# INA169_Breakout.net
KiCad netlist of a schematic drawn in EAGLE
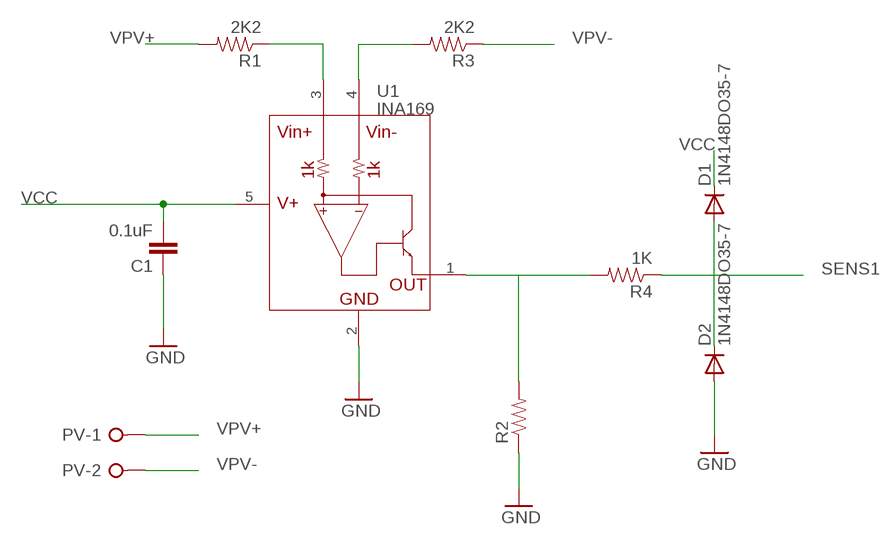
[diagram p0: schematic, sheet 1]
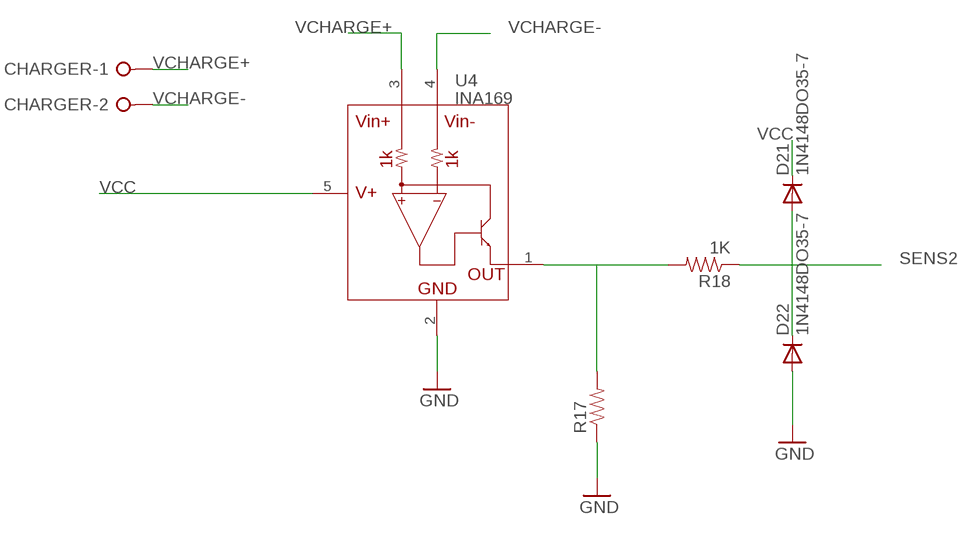
[diagram p1: schematic, sheet 2]
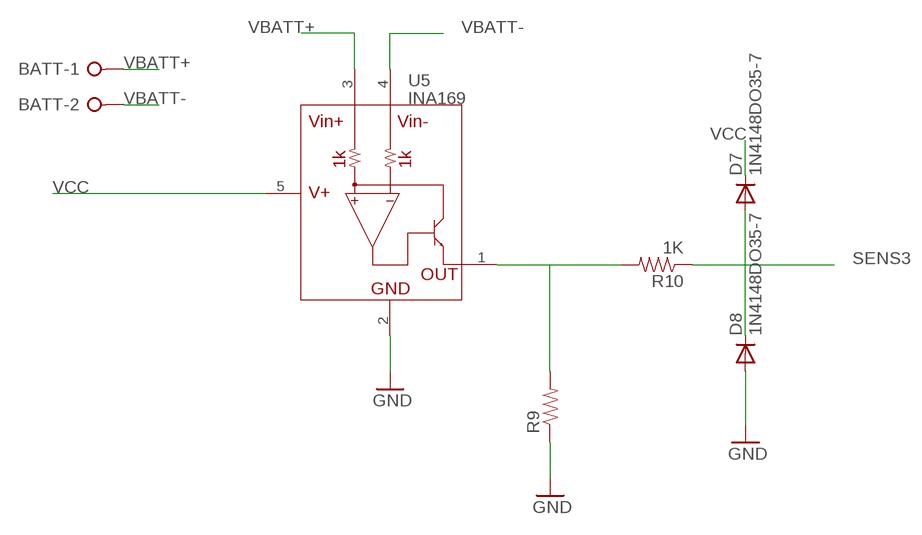
[diagram p2: schematic, sheet 3]
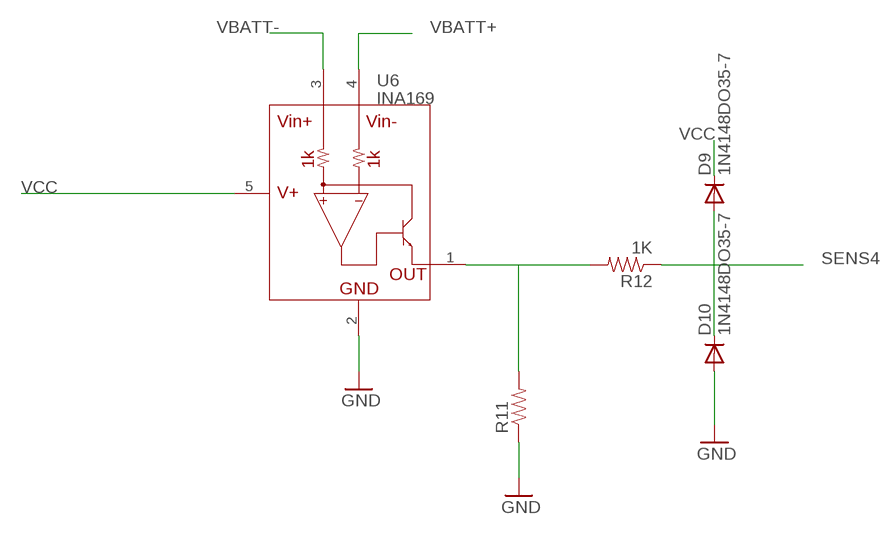
[diagram p3: schematic, sheet 4]
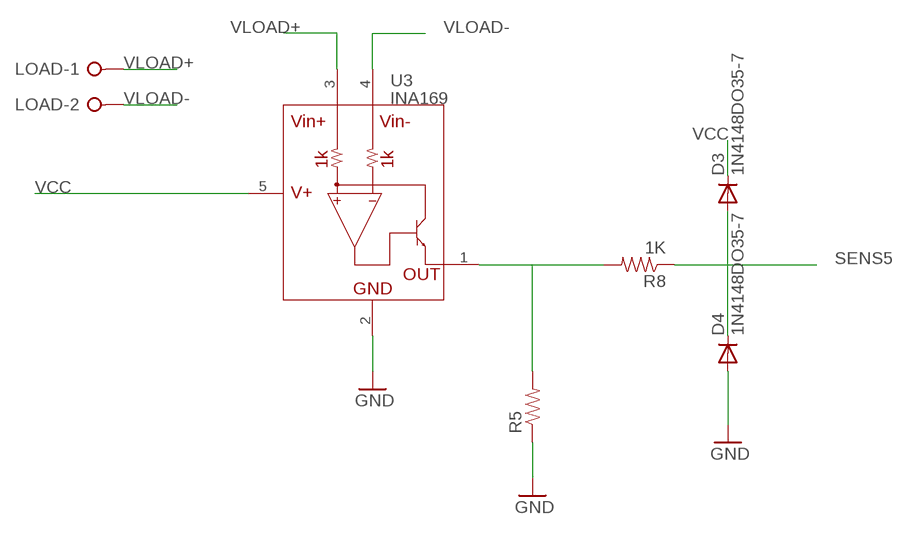
[diagram p4: schematic, sheet 5]
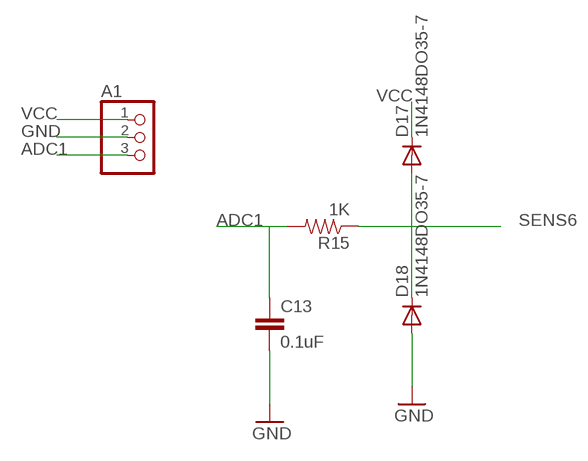
[diagram p5: schematic, sheet 6]
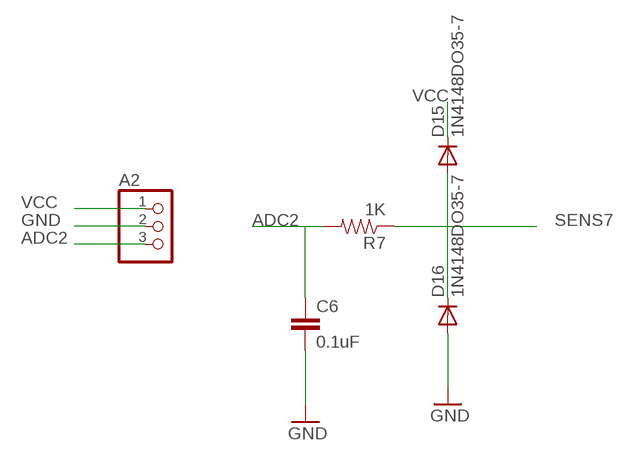
[diagram p6: schematic, sheet 7]
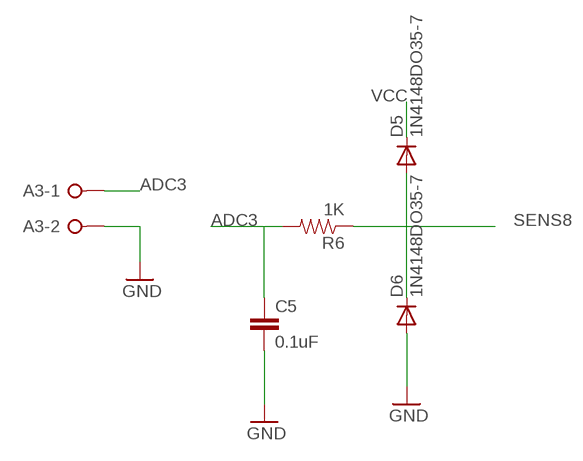
[diagram p7: schematic, sheet 8]
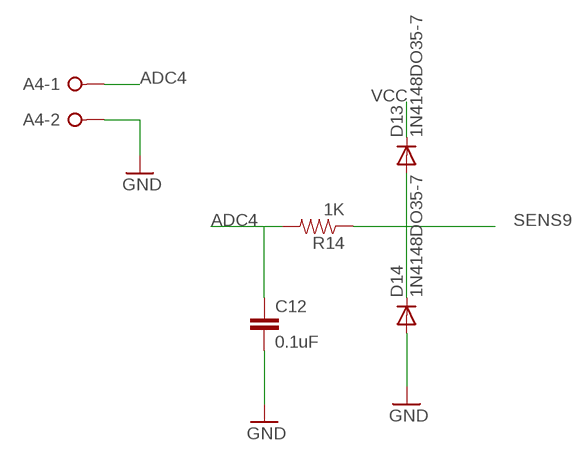
[diagram p8: schematic, sheet 9]
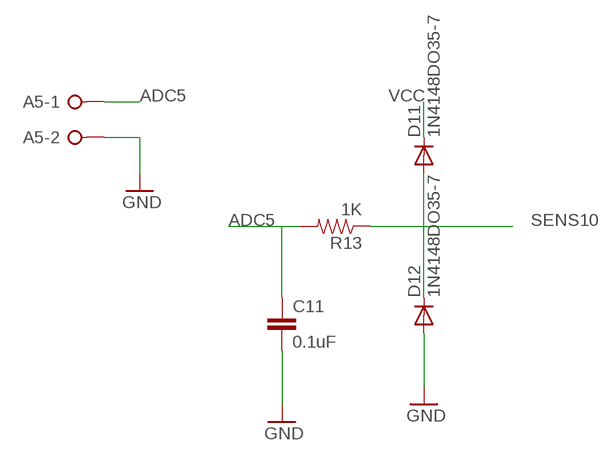
[diagram p9: schematic, sheet 10]
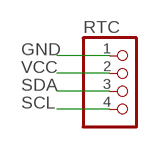
[diagram p10: schematic, sheet 11]
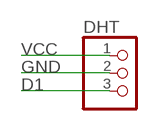
[diagram p11: schematic, sheet 12]
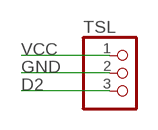
[diagram p12: schematic, sheet 13]
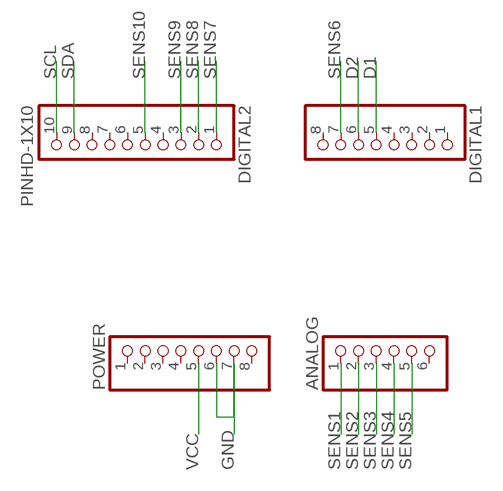
[diagram p13: schematic, sheet 14]

(export (version "E")
  (design (tool "Eeschema 10.0.6"))
  (components
    (comp (ref "CHARGER")
      (value "W237-02P")
      (footprint "eagle-import:W237-132")
      (libsource (lib "eagle-import") (part "W237-02P"))
    )
    (comp (ref "D21")
      (value "1N4148DO35-7")
      (footprint "eagle-import:DO35-7")
      (libsource (lib "eagle-import") (part "1N4148DO35-7"))
    )
    (comp (ref "D22")
      (value "1N4148DO35-7")
      (footprint "eagle-import:DO35-7")
      (libsource (lib "eagle-import") (part "1N4148DO35-7"))
    )
    (comp (ref "R17")
      (value "RESISTOR0603")
      (footprint "eagle-import:0603-RES")
      (fields (field (name "TOL") "1%"))
      (libsource (lib "eagle-import") (part "RESISTOR0603"))
    )
    (comp (ref "R18")
      (value "1K")
      (footprint "eagle-import:0603-RES")
      (fields (field (name "TOL") "1%"))
      (libsource (lib "eagle-import") (part "RESISTOR0603"))
    )
    (comp (ref "U4")
      (value "INA169")
      (footprint "eagle-import:SOT23-5")
      (libsource (lib "eagle-import") (part "INA169"))
    )
    (comp (ref "A2")
      (value "PINHD-1X3")
      (footprint "eagle-import:1X03")
      (libsource (lib "eagle-import") (part "PINHD-1X3"))
    )
    (comp (ref "C6")
      (value "0.1uF")
      (footprint "eagle-import:0603-CAP")
      (libsource (lib "eagle-import") (part "CAP0603-CAP"))
    )
    (comp (ref "D15")
      (value "1N4148DO35-7")
      (footprint "eagle-import:DO35-7")
      (libsource (lib "eagle-import") (part "1N4148DO35-7"))
    )
    (comp (ref "D16")
      (value "1N4148DO35-7")
      (footprint "eagle-import:DO35-7")
      (libsource (lib "eagle-import") (part "1N4148DO35-7"))
    )
    (comp (ref "R7")
      (value "1K")
      (footprint "eagle-import:0603-RES")
      (fields (field (name "TOL") "1%"))
      (libsource (lib "eagle-import") (part "RESISTOR0603"))
    )
    (comp (ref "D3")
      (value "1N4148DO35-7")
      (footprint "eagle-import:DO35-7")
      (libsource (lib "eagle-import") (part "1N4148DO35-7"))
    )
    (comp (ref "D4")
      (value "1N4148DO35-7")
      (footprint "eagle-import:DO35-7")
      (libsource (lib "eagle-import") (part "1N4148DO35-7"))
    )
    (comp (ref "LOAD")
      (value "W237-02P")
      (footprint "eagle-import:W237-132")
      (libsource (lib "eagle-import") (part "W237-02P"))
    )
    (comp (ref "R5")
      (value "RESISTOR0603")
      (footprint "eagle-import:0603-RES")
      (fields (field (name "TOL") "1%"))
      (libsource (lib "eagle-import") (part "RESISTOR0603"))
    )
    (comp (ref "R8")
      (value "1K")
      (footprint "eagle-import:0603-RES")
      (fields (field (name "TOL") "1%"))
      (libsource (lib "eagle-import") (part "RESISTOR0603"))
    )
    (comp (ref "U3")
      (value "INA169")
      (footprint "eagle-import:SOT23-5")
      (libsource (lib "eagle-import") (part "INA169"))
    )
    (comp (ref "A4")
      (value "W237-02P")
      (footprint "eagle-import:W237-132")
      (libsource (lib "eagle-import") (part "W237-02P"))
    )
    (comp (ref "C12")
      (value "0.1uF")
      (footprint "eagle-import:0603-CAP")
      (libsource (lib "eagle-import") (part "CAP0603-CAP"))
    )
    (comp (ref "D13")
      (value "1N4148DO35-7")
      (footprint "eagle-import:DO35-7")
      (libsource (lib "eagle-import") (part "1N4148DO35-7"))
    )
    (comp (ref "D14")
      (value "1N4148DO35-7")
      (footprint "eagle-import:DO35-7")
      (libsource (lib "eagle-import") (part "1N4148DO35-7"))
    )
    (comp (ref "R14")
      (value "1K")
      (footprint "eagle-import:0603-RES")
      (fields (field (name "TOL") "1%"))
      (libsource (lib "eagle-import") (part "RESISTOR0603"))
    )
    (comp (ref "ANALOG")
      (value "PINHD-1X6B")
      (footprint "eagle-import:1X06-BIG")
      (libsource (lib "eagle-import") (part "PINHD-1X6B"))
    )
    (comp (ref "DIGITAL1")
      (value "PINHD-1X8BIG")
      (footprint "eagle-import:1X08-BIG")
      (libsource (lib "eagle-import") (part "PINHD-1X8BIG"))
    )
    (comp (ref "DIGITAL2")
      (value "PINHD-1X10")
      (footprint "eagle-import:1X10-BIG")
      (libsource (lib "eagle-import") (part "PINHD-1X10"))
    )
    (comp (ref "POWER")
      (value "PINHD-1X8BIG")
      (footprint "eagle-import:1X08-BIG")
      (libsource (lib "eagle-import") (part "PINHD-1X8BIG"))
    )
    (comp (ref "A3")
      (value "W237-02P")
      (footprint "eagle-import:W237-132")
      (libsource (lib "eagle-import") (part "W237-02P"))
    )
    (comp (ref "C5")
      (value "0.1uF")
      (footprint "eagle-import:0603-CAP")
      (libsource (lib "eagle-import") (part "CAP0603-CAP"))
    )
    (comp (ref "D5")
      (value "1N4148DO35-7")
      (footprint "eagle-import:DO35-7")
      (libsource (lib "eagle-import") (part "1N4148DO35-7"))
    )
    (comp (ref "D6")
      (value "1N4148DO35-7")
      (footprint "eagle-import:DO35-7")
      (libsource (lib "eagle-import") (part "1N4148DO35-7"))
    )
    (comp (ref "R6")
      (value "1K")
      (footprint "eagle-import:0603-RES")
      (fields (field (name "TOL") "1%"))
      (libsource (lib "eagle-import") (part "RESISTOR0603"))
    )
    (comp (ref "D9")
      (value "1N4148DO35-7")
      (footprint "eagle-import:DO35-7")
      (libsource (lib "eagle-import") (part "1N4148DO35-7"))
    )
    (comp (ref "D10")
      (value "1N4148DO35-7")
      (footprint "eagle-import:DO35-7")
      (libsource (lib "eagle-import") (part "1N4148DO35-7"))
    )
    (comp (ref "R11")
      (value "RESISTOR0603")
      (footprint "eagle-import:0603-RES")
      (fields (field (name "TOL") "1%"))
      (libsource (lib "eagle-import") (part "RESISTOR0603"))
    )
    (comp (ref "R12")
      (value "1K")
      (footprint "eagle-import:0603-RES")
      (fields (field (name "TOL") "1%"))
      (libsource (lib "eagle-import") (part "RESISTOR0603"))
    )
    (comp (ref "U6")
      (value "INA169")
      (footprint "eagle-import:SOT23-5")
      (libsource (lib "eagle-import") (part "INA169"))
    )
    (comp (ref "TSL")
      (value "PINHD-1X3")
      (footprint "eagle-import:1X03")
      (libsource (lib "eagle-import") (part "PINHD-1X3"))
    )
    (comp (ref "RTC")
      (value "PINHD-1X4/90")
      (footprint "eagle-import:1X04_90")
      (libsource (lib "eagle-import") (part "PINHD-1X4/90"))
    )
    (comp (ref "A5")
      (value "W237-02P")
      (footprint "eagle-import:W237-132")
      (libsource (lib "eagle-import") (part "W237-02P"))
    )
    (comp (ref "C11")
      (value "0.1uF")
      (footprint "eagle-import:0603-CAP")
      (libsource (lib "eagle-import") (part "CAP0603-CAP"))
    )
    (comp (ref "D11")
      (value "1N4148DO35-7")
      (footprint "eagle-import:DO35-7")
      (libsource (lib "eagle-import") (part "1N4148DO35-7"))
    )
    (comp (ref "D12")
      (value "1N4148DO35-7")
      (footprint "eagle-import:DO35-7")
      (libsource (lib "eagle-import") (part "1N4148DO35-7"))
    )
    (comp (ref "R13")
      (value "1K")
      (footprint "eagle-import:0603-RES")
      (fields (field (name "TOL") "1%"))
      (libsource (lib "eagle-import") (part "RESISTOR0603"))
    )
    (comp (ref "BATT")
      (value "W237-02P")
      (footprint "eagle-import:W237-132")
      (libsource (lib "eagle-import") (part "W237-02P"))
    )
    (comp (ref "D7")
      (value "1N4148DO35-7")
      (footprint "eagle-import:DO35-7")
      (libsource (lib "eagle-import") (part "1N4148DO35-7"))
    )
    (comp (ref "D8")
      (value "1N4148DO35-7")
      (footprint "eagle-import:DO35-7")
      (libsource (lib "eagle-import") (part "1N4148DO35-7"))
    )
    (comp (ref "R9")
      (value "RESISTOR0603")
      (footprint "eagle-import:0603-RES")
      (fields (field (name "TOL") "1%"))
      (libsource (lib "eagle-import") (part "RESISTOR0603"))
    )
    (comp (ref "R10")
      (value "1K")
      (footprint "eagle-import:0603-RES")
      (fields (field (name "TOL") "1%"))
      (libsource (lib "eagle-import") (part "RESISTOR0603"))
    )
    (comp (ref "U5")
      (value "INA169")
      (footprint "eagle-import:SOT23-5")
      (libsource (lib "eagle-import") (part "INA169"))
    )
    (comp (ref "C1")
      (value "0.1uF")
      (footprint "eagle-import:0603-CAP")
      (libsource (lib "eagle-import") (part "CAP0603-CAP"))
    )
    (comp (ref "D1")
      (value "1N4148DO35-7")
      (footprint "eagle-import:DO35-7")
      (libsource (lib "eagle-import") (part "1N4148DO35-7"))
    )
    (comp (ref "D2")
      (value "1N4148DO35-7")
      (footprint "eagle-import:DO35-7")
      (libsource (lib "eagle-import") (part "1N4148DO35-7"))
    )
    (comp (ref "PV")
      (value "W237-02P")
      (footprint "eagle-import:W237-132")
      (libsource (lib "eagle-import") (part "W237-02P"))
    )
    (comp (ref "R1")
      (value "2K2")
      (footprint "eagle-import:0603-RES")
      (fields (field (name "TOL") "1%"))
      (libsource (lib "eagle-import") (part "RESISTOR0603"))
    )
    (comp (ref "R2")
      (value "RESISTOR0603")
      (footprint "eagle-import:0603-RES")
      (fields (field (name "TOL") "1%"))
      (libsource (lib "eagle-import") (part "RESISTOR0603"))
    )
    (comp (ref "R3")
      (value "2K2")
      (footprint "eagle-import:0603-RES")
      (fields (field (name "TOL") "1%"))
      (libsource (lib "eagle-import") (part "RESISTOR0603"))
    )
    (comp (ref "R4")
      (value "1K")
      (footprint "eagle-import:0603-RES")
      (fields (field (name "TOL") "1%"))
      (libsource (lib "eagle-import") (part "RESISTOR0603"))
    )
    (comp (ref "U1")
      (value "INA169")
      (footprint "eagle-import:SOT23-5")
      (libsource (lib "eagle-import") (part "INA169"))
    )
    (comp (ref "DHT")
      (value "PINHD-1X3")
      (footprint "eagle-import:1X03")
      (libsource (lib "eagle-import") (part "PINHD-1X3"))
    )
    (comp (ref "A1")
      (value "PINHD-1X3")
      (footprint "eagle-import:1X03")
      (libsource (lib "eagle-import") (part "PINHD-1X3"))
    )
    (comp (ref "C13")
      (value "0.1uF")
      (footprint "eagle-import:0603-CAP")
      (libsource (lib "eagle-import") (part "CAP0603-CAP"))
    )
    (comp (ref "D17")
      (value "1N4148DO35-7")
      (footprint "eagle-import:DO35-7")
      (libsource (lib "eagle-import") (part "1N4148DO35-7"))
    )
    (comp (ref "D18")
      (value "1N4148DO35-7")
      (footprint "eagle-import:DO35-7")
      (libsource (lib "eagle-import") (part "1N4148DO35-7"))
    )
    (comp (ref "R15")
      (value "1K")
      (footprint "eagle-import:0603-RES")
      (fields (field (name "TOL") "1%"))
      (libsource (lib "eagle-import") (part "RESISTOR0603"))
    )
  )
  (nets
    (net (code "1") (name "ADC1") (class "Default")
      (node (ref "A1") (pin "3") (pinfunction "3_3") (pintype "passive"))
      (node (ref "C13") (pin "1") (pinfunction "1_1") (pintype "passive"))
      (node (ref "R15") (pin "2") (pinfunction "2_2") (pintype "passive"))
    )
    (net (code "2") (name "ADC2") (class "Default")
      (node (ref "A2") (pin "3") (pinfunction "3_3") (pintype "passive"))
      (node (ref "C6") (pin "1") (pinfunction "1_1") (pintype "passive"))
      (node (ref "R7") (pin "2") (pinfunction "2_2") (pintype "passive"))
    )
    (net (code "3") (name "ADC3") (class "Default")
      (node (ref "A3") (pin "1") (pinfunction "KL_1") (pintype "passive"))
      (node (ref "C5") (pin "1") (pinfunction "1_1") (pintype "passive"))
      (node (ref "R6") (pin "2") (pinfunction "2_2") (pintype "passive"))
    )
    (net (code "4") (name "ADC4") (class "Default")
      (node (ref "A4") (pin "1") (pinfunction "KL_1") (pintype "passive"))
      (node (ref "C12") (pin "1") (pinfunction "1_1") (pintype "passive"))
      (node (ref "R14") (pin "2") (pinfunction "2_2") (pintype "passive"))
    )
    (net (code "5") (name "ADC5") (class "Default")
      (node (ref "A5") (pin "1") (pinfunction "KL_1") (pintype "passive"))
      (node (ref "C11") (pin "1") (pinfunction "1_1") (pintype "passive"))
      (node (ref "R13") (pin "2") (pinfunction "2_2") (pintype "passive"))
    )
    (net (code "6") (name "D1") (class "Default")
      (node (ref "DHT") (pin "3") (pinfunction "3_3") (pintype "passive"))
      (node (ref "DIGITAL1") (pin "5") (pinfunction "5_5") (pintype "passive"))
    )
    (net (code "7") (name "D2") (class "Default")
      (node (ref "DIGITAL1") (pin "6") (pinfunction "6_6") (pintype "passive"))
      (node (ref "TSL") (pin "3") (pinfunction "3_3") (pintype "passive"))
    )
    (net (code "8") (name "GND") (class "Default")
      (node (ref "A1") (pin "2") (pinfunction "2_2") (pintype "passive"))
      (node (ref "A2") (pin "2") (pinfunction "2_2") (pintype "passive"))
      (node (ref "A3") (pin "2") (pinfunction "KL_2") (pintype "passive"))
      (node (ref "A4") (pin "2") (pinfunction "KL_2") (pintype "passive"))
      (node (ref "A5") (pin "2") (pinfunction "KL_2") (pintype "passive"))
      (node (ref "C1") (pin "1") (pinfunction "1_1") (pintype "passive"))
      (node (ref "C11") (pin "2") (pinfunction "2_2") (pintype "passive"))
      (node (ref "C12") (pin "2") (pinfunction "2_2") (pintype "passive"))
      (node (ref "C13") (pin "2") (pinfunction "2_2") (pintype "passive"))
      (node (ref "C5") (pin "2") (pinfunction "2_2") (pintype "passive"))
      (node (ref "C6") (pin "2") (pinfunction "2_2") (pintype "passive"))
      (node (ref "D10") (pin "A") (pinfunction "A_A") (pintype "passive"))
      (node (ref "D12") (pin "A") (pinfunction "A_A") (pintype "passive"))
      (node (ref "D14") (pin "A") (pinfunction "A_A") (pintype "passive"))
      (node (ref "D16") (pin "A") (pinfunction "A_A") (pintype "passive"))
      (node (ref "D18") (pin "A") (pinfunction "A_A") (pintype "passive"))
      (node (ref "D2") (pin "A") (pinfunction "A_A") (pintype "passive"))
      (node (ref "D22") (pin "A") (pinfunction "A_A") (pintype "passive"))
      (node (ref "D4") (pin "A") (pinfunction "A_A") (pintype "passive"))
      (node (ref "D6") (pin "A") (pinfunction "A_A") (pintype "passive"))
      (node (ref "D8") (pin "A") (pinfunction "A_A") (pintype "passive"))
      (node (ref "DHT") (pin "2") (pinfunction "2_2") (pintype "passive"))
      (node (ref "POWER") (pin "6") (pinfunction "6_6") (pintype "passive"))
      (node (ref "POWER") (pin "7") (pinfunction "7_7") (pintype "passive"))
      (node (ref "R11") (pin "1") (pinfunction "1_1") (pintype "passive"))
      (node (ref "R17") (pin "1") (pinfunction "1_1") (pintype "passive"))
      (node (ref "R2") (pin "1") (pinfunction "1_1") (pintype "passive"))
      (node (ref "R5") (pin "1") (pinfunction "1_1") (pintype "passive"))
      (node (ref "R9") (pin "1") (pinfunction "1_1") (pintype "passive"))
      (node (ref "RTC") (pin "1") (pinfunction "1_1") (pintype "passive"))
      (node (ref "TSL") (pin "2") (pinfunction "2_2") (pintype "passive"))
      (node (ref "U1") (pin "2") (pinfunction "GND_2") (pintype "bidirectional"))
      (node (ref "U3") (pin "2") (pinfunction "GND_2") (pintype "bidirectional"))
      (node (ref "U4") (pin "2") (pinfunction "GND_2") (pintype "bidirectional"))
      (node (ref "U5") (pin "2") (pinfunction "GND_2") (pintype "bidirectional"))
      (node (ref "U6") (pin "2") (pinfunction "GND_2") (pintype "bidirectional"))
    )
    (net (code "9") (name "Net-(U1-OUT)") (class "Default")
      (node (ref "R2") (pin "2") (pinfunction "2_2") (pintype "passive"))
      (node (ref "R4") (pin "2") (pinfunction "2_2") (pintype "passive"))
      (node (ref "U1") (pin "1") (pinfunction "OUT_1") (pintype "bidirectional"))
    )
    (net (code "10") (name "Net-(U1-VIN+)") (class "Default")
      (node (ref "R1") (pin "1") (pinfunction "1_1") (pintype "passive"))
      (node (ref "U1") (pin "3") (pinfunction "VIN+_3") (pintype "bidirectional"))
    )
    (net (code "11") (name "Net-(U1-VIN-)") (class "Default")
      (node (ref "R3") (pin "2") (pinfunction "2_2") (pintype "passive"))
      (node (ref "U1") (pin "4") (pinfunction "VIN-_4") (pintype "bidirectional"))
    )
    (net (code "12") (name "Net-(U3-OUT)") (class "Default")
      (node (ref "R5") (pin "2") (pinfunction "2_2") (pintype "passive"))
      (node (ref "R8") (pin "2") (pinfunction "2_2") (pintype "passive"))
      (node (ref "U3") (pin "1") (pinfunction "OUT_1") (pintype "bidirectional"))
    )
    (net (code "13") (name "Net-(U4-OUT)") (class "Default")
      (node (ref "R17") (pin "2") (pinfunction "2_2") (pintype "passive"))
      (node (ref "R18") (pin "2") (pinfunction "2_2") (pintype "passive"))
      (node (ref "U4") (pin "1") (pinfunction "OUT_1") (pintype "bidirectional"))
    )
    (net (code "14") (name "Net-(U5-OUT)") (class "Default")
      (node (ref "R10") (pin "2") (pinfunction "2_2") (pintype "passive"))
      (node (ref "R9") (pin "2") (pinfunction "2_2") (pintype "passive"))
      (node (ref "U5") (pin "1") (pinfunction "OUT_1") (pintype "bidirectional"))
    )
    (net (code "15") (name "Net-(U6-OUT)") (class "Default")
      (node (ref "R11") (pin "2") (pinfunction "2_2") (pintype "passive"))
      (node (ref "R12") (pin "2") (pinfunction "2_2") (pintype "passive"))
      (node (ref "U6") (pin "1") (pinfunction "OUT_1") (pintype "bidirectional"))
    )
    (net (code "16") (name "SCL") (class "Default")
      (node (ref "DIGITAL2") (pin "10") (pinfunction "10_10") (pintype "passive"))
      (node (ref "RTC") (pin "4") (pinfunction "4_4") (pintype "passive"))
    )
    (net (code "17") (name "SDA") (class "Default")
      (node (ref "DIGITAL2") (pin "9") (pinfunction "9_9") (pintype "passive"))
      (node (ref "RTC") (pin "3") (pinfunction "3_3") (pintype "passive"))
    )
    (net (code "18") (name "SENS1") (class "Default")
      (node (ref "ANALOG") (pin "1") (pinfunction "1_1") (pintype "passive"))
      (node (ref "D1") (pin "A") (pinfunction "A_A") (pintype "passive"))
      (node (ref "D2") (pin "C") (pinfunction "C_C") (pintype "passive"))
      (node (ref "R4") (pin "1") (pinfunction "1_1") (pintype "passive"))
    )
    (net (code "19") (name "SENS2") (class "Default")
      (node (ref "ANALOG") (pin "2") (pinfunction "2_2") (pintype "passive"))
      (node (ref "D21") (pin "A") (pinfunction "A_A") (pintype "passive"))
      (node (ref "D22") (pin "C") (pinfunction "C_C") (pintype "passive"))
      (node (ref "R18") (pin "1") (pinfunction "1_1") (pintype "passive"))
    )
    (net (code "20") (name "SENS3") (class "Default")
      (node (ref "ANALOG") (pin "3") (pinfunction "3_3") (pintype "passive"))
      (node (ref "D7") (pin "A") (pinfunction "A_A") (pintype "passive"))
      (node (ref "D8") (pin "C") (pinfunction "C_C") (pintype "passive"))
      (node (ref "R10") (pin "1") (pinfunction "1_1") (pintype "passive"))
    )
    (net (code "21") (name "SENS4") (class "Default")
      (node (ref "ANALOG") (pin "4") (pinfunction "4_4") (pintype "passive"))
      (node (ref "D10") (pin "C") (pinfunction "C_C") (pintype "passive"))
      (node (ref "D9") (pin "A") (pinfunction "A_A") (pintype "passive"))
      (node (ref "R12") (pin "1") (pinfunction "1_1") (pintype "passive"))
    )
    (net (code "22") (name "SENS5") (class "Default")
      (node (ref "ANALOG") (pin "5") (pinfunction "5_5") (pintype "passive"))
      (node (ref "D3") (pin "A") (pinfunction "A_A") (pintype "passive"))
      (node (ref "D4") (pin "C") (pinfunction "C_C") (pintype "passive"))
      (node (ref "R8") (pin "1") (pinfunction "1_1") (pintype "passive"))
    )
    (net (code "23") (name "SENS6") (class "Default")
      (node (ref "D17") (pin "A") (pinfunction "A_A") (pintype "passive"))
      (node (ref "D18") (pin "C") (pinfunction "C_C") (pintype "passive"))
      (node (ref "DIGITAL1") (pin "7") (pinfunction "7_7") (pintype "passive"))
      (node (ref "R15") (pin "1") (pinfunction "1_1") (pintype "passive"))
    )
    (net (code "24") (name "SENS7") (class "Default")
      (node (ref "D15") (pin "A") (pinfunction "A_A") (pintype "passive"))
      (node (ref "D16") (pin "C") (pinfunction "C_C") (pintype "passive"))
      (node (ref "DIGITAL2") (pin "1") (pinfunction "1_1") (pintype "passive"))
      (node (ref "R7") (pin "1") (pinfunction "1_1") (pintype "passive"))
    )
    (net (code "25") (name "SENS8") (class "Default")
      (node (ref "D5") (pin "A") (pinfunction "A_A") (pintype "passive"))
      (node (ref "D6") (pin "C") (pinfunction "C_C") (pintype "passive"))
      (node (ref "DIGITAL2") (pin "2") (pinfunction "2_2") (pintype "passive"))
      (node (ref "R6") (pin "1") (pinfunction "1_1") (pintype "passive"))
    )
    (net (code "26") (name "SENS9") (class "Default")
      (node (ref "D13") (pin "A") (pinfunction "A_A") (pintype "passive"))
      (node (ref "D14") (pin "C") (pinfunction "C_C") (pintype "passive"))
      (node (ref "DIGITAL2") (pin "3") (pinfunction "3_3") (pintype "passive"))
      (node (ref "R14") (pin "1") (pinfunction "1_1") (pintype "passive"))
    )
    (net (code "27") (name "SENS10") (class "Default")
      (node (ref "D11") (pin "A") (pinfunction "A_A") (pintype "passive"))
      (node (ref "D12") (pin "C") (pinfunction "C_C") (pintype "passive"))
      (node (ref "DIGITAL2") (pin "5") (pinfunction "5_5") (pintype "passive"))
      (node (ref "R13") (pin "1") (pinfunction "1_1") (pintype "passive"))
    )
    (net (code "28") (name "VBATT+") (class "Default")
      (node (ref "BATT") (pin "1") (pinfunction "KL_1") (pintype "passive"))
      (node (ref "U5") (pin "3") (pinfunction "VIN+_3") (pintype "bidirectional"))
      (node (ref "U6") (pin "4") (pinfunction "VIN-_4") (pintype "bidirectional"))
    )
    (net (code "29") (name "VBATT-") (class "Default")
      (node (ref "BATT") (pin "2") (pinfunction "KL_2") (pintype "passive"))
      (node (ref "U5") (pin "4") (pinfunction "VIN-_4") (pintype "bidirectional"))
      (node (ref "U6") (pin "3") (pinfunction "VIN+_3") (pintype "bidirectional"))
    )
    (net (code "30") (name "VCC") (class "Default")
      (node (ref "A1") (pin "1") (pinfunction "1_1") (pintype "passive"))
      (node (ref "A2") (pin "1") (pinfunction "1_1") (pintype "passive"))
      (node (ref "C1") (pin "2") (pinfunction "2_2") (pintype "passive"))
      (node (ref "D1") (pin "C") (pinfunction "C_C") (pintype "passive"))
      (node (ref "D11") (pin "C") (pinfunction "C_C") (pintype "passive"))
      (node (ref "D13") (pin "C") (pinfunction "C_C") (pintype "passive"))
      (node (ref "D15") (pin "C") (pinfunction "C_C") (pintype "passive"))
      (node (ref "D17") (pin "C") (pinfunction "C_C") (pintype "passive"))
      (node (ref "D21") (pin "C") (pinfunction "C_C") (pintype "passive"))
      (node (ref "D3") (pin "C") (pinfunction "C_C") (pintype "passive"))
      (node (ref "D5") (pin "C") (pinfunction "C_C") (pintype "passive"))
      (node (ref "D7") (pin "C") (pinfunction "C_C") (pintype "passive"))
      (node (ref "D9") (pin "C") (pinfunction "C_C") (pintype "passive"))
      (node (ref "DHT") (pin "1") (pinfunction "1_1") (pintype "passive"))
      (node (ref "POWER") (pin "5") (pinfunction "5_5") (pintype "passive"))
      (node (ref "RTC") (pin "2") (pinfunction "2_2") (pintype "passive"))
      (node (ref "TSL") (pin "1") (pinfunction "1_1") (pintype "passive"))
      (node (ref "U1") (pin "5") (pinfunction "V+_5") (pintype "bidirectional"))
      (node (ref "U3") (pin "5") (pinfunction "V+_5") (pintype "bidirectional"))
      (node (ref "U4") (pin "5") (pinfunction "V+_5") (pintype "bidirectional"))
      (node (ref "U5") (pin "5") (pinfunction "V+_5") (pintype "bidirectional"))
      (node (ref "U6") (pin "5") (pinfunction "V+_5") (pintype "bidirectional"))
    )
    (net (code "31") (name "VCHARGE+") (class "Default")
      (node (ref "CHARGER") (pin "1") (pinfunction "KL_1") (pintype "passive"))
      (node (ref "U4") (pin "3") (pinfunction "VIN+_3") (pintype "bidirectional"))
    )
    (net (code "32") (name "VCHARGE-") (class "Default")
      (node (ref "CHARGER") (pin "2") (pinfunction "KL_2") (pintype "passive"))
      (node (ref "U4") (pin "4") (pinfunction "VIN-_4") (pintype "bidirectional"))
    )
    (net (code "33") (name "VLOAD+") (class "Default")
      (node (ref "LOAD") (pin "1") (pinfunction "KL_1") (pintype "passive"))
      (node (ref "U3") (pin "3") (pinfunction "VIN+_3") (pintype "bidirectional"))
    )
    (net (code "34") (name "VLOAD-") (class "Default")
      (node (ref "LOAD") (pin "2") (pinfunction "KL_2") (pintype "passive"))
      (node (ref "U3") (pin "4") (pinfunction "VIN-_4") (pintype "bidirectional"))
    )
    (net (code "35") (name "VPV+") (class "Default")
      (node (ref "PV") (pin "1") (pinfunction "KL_1") (pintype "passive"))
      (node (ref "R1") (pin "2") (pinfunction "2_2") (pintype "passive"))
    )
    (net (code "36") (name "VPV-") (class "Default")
      (node (ref "PV") (pin "2") (pinfunction "KL_2") (pintype "passive"))
      (node (ref "R3") (pin "1") (pinfunction "1_1") (pintype "passive"))
    )
    (net (code "37") (name "unconnected-(ANALOG-Pad6)") (class "Default")
      (node (ref "ANALOG") (pin "6") (pinfunction "6_6") (pintype "passive"))
    )
    (net (code "38") (name "unconnected-(DIGITAL1-Pad1)") (class "Default")
      (node (ref "DIGITAL1") (pin "1") (pinfunction "1_1") (pintype "passive"))
    )
    (net (code "39") (name "unconnected-(DIGITAL1-Pad2)") (class "Default")
      (node (ref "DIGITAL1") (pin "2") (pinfunction "2_2") (pintype "passive"))
    )
    (net (code "40") (name "unconnected-(DIGITAL1-Pad3)") (class "Default")
      (node (ref "DIGITAL1") (pin "3") (pinfunction "3_3") (pintype "passive"))
    )
    (net (code "41") (name "unconnected-(DIGITAL1-Pad4)") (class "Default")
      (node (ref "DIGITAL1") (pin "4") (pinfunction "4_4") (pintype "passive"))
    )
    (net (code "42") (name "unconnected-(DIGITAL1-Pad8)") (class "Default")
      (node (ref "DIGITAL1") (pin "8") (pinfunction "8_8") (pintype "passive"))
    )
    (net (code "43") (name "unconnected-(DIGITAL2-Pad4)") (class "Default")
      (node (ref "DIGITAL2") (pin "4") (pinfunction "4_4") (pintype "passive"))
    )
    (net (code "44") (name "unconnected-(DIGITAL2-Pad6)") (class "Default")
      (node (ref "DIGITAL2") (pin "6") (pinfunction "6_6") (pintype "passive"))
    )
    (net (code "45") (name "unconnected-(DIGITAL2-Pad7)") (class "Default")
      (node (ref "DIGITAL2") (pin "7") (pinfunction "7_7") (pintype "passive"))
    )
    (net (code "46") (name "unconnected-(DIGITAL2-Pad8)") (class "Default")
      (node (ref "DIGITAL2") (pin "8") (pinfunction "8_8") (pintype "passive"))
    )
    (net (code "47") (name "unconnected-(POWER-Pad1)") (class "Default")
      (node (ref "POWER") (pin "1") (pinfunction "1_1") (pintype "passive"))
    )
    (net (code "48") (name "unconnected-(POWER-Pad2)") (class "Default")
      (node (ref "POWER") (pin "2") (pinfunction "2_2") (pintype "passive"))
    )
    (net (code "49") (name "unconnected-(POWER-Pad3)") (class "Default")
      (node (ref "POWER") (pin "3") (pinfunction "3_3") (pintype "passive"))
    )
    (net (code "50") (name "unconnected-(POWER-Pad4)") (class "Default")
      (node (ref "POWER") (pin "4") (pinfunction "4_4") (pintype "passive"))
    )
    (net (code "51") (name "unconnected-(POWER-Pad8)") (class "Default")
      (node (ref "POWER") (pin "8") (pinfunction "8_8") (pintype "passive"))
    )
  )
)
